# GPO.net
KiCad netlist of a schematic drawn in Altium Designer
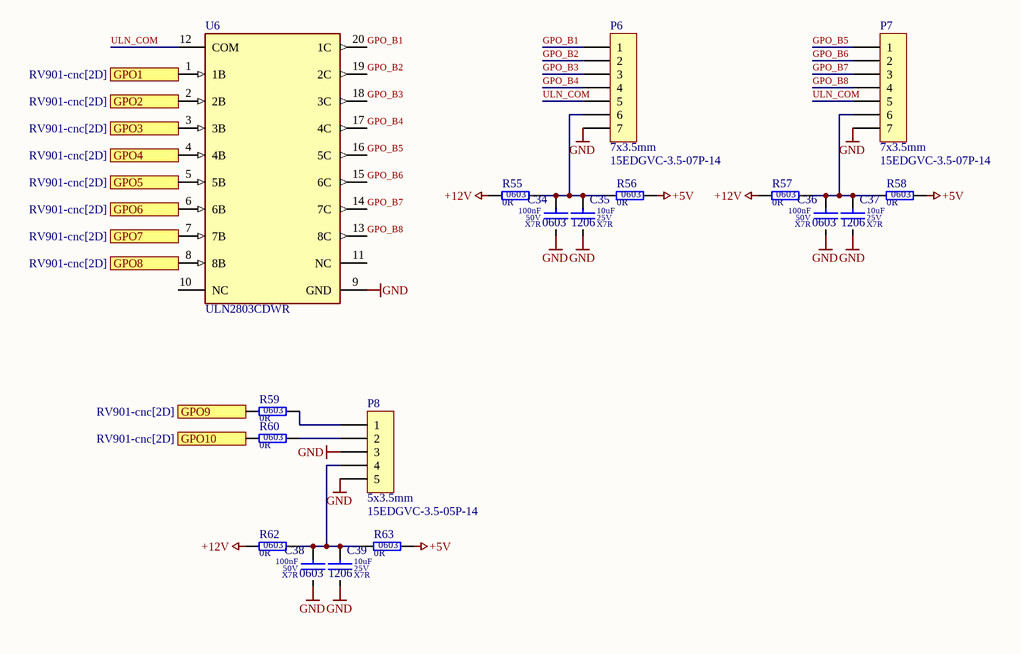
[diagram p0: GPO.SchDoc]

(export (version "E")
  (design (tool "Eeschema 10.0.6"))
  (components
    (comp (ref "C34")
      (value "100nF")
      (footprint "C_0603_1608")
      (description "Capacitor")
      (fields
        (field (name "DIELECTRIC") "X7R")
        (field (name "VOLTAGE") "50V")
        (field (name "SCH_FOOTPRINT") "0603")
        (field (name "PART NUMBER") "C_100nF_50V_X7R_0603_5")
        (field (name "MANUFACTURER") "Samsung")
      )
      (libsource (lib "Library") (part "C"))
    )
    (comp (ref "C35")
      (value "10uF")
      (footprint "C_1206_3216")
      (description "Capacitor")
      (fields
        (field (name "DIELECTRIC") "X7R")
        (field (name "VOLTAGE") "25V")
        (field (name "SCH_FOOTPRINT") "1206")
        (field (name "PART NUMBER") "C_10uF_25V_X7R_1206_10")
        (field (name "MANUFACTURER") "Samsung")
      )
      (libsource (lib "Library") (part "C"))
    )
    (comp (ref "C36")
      (value "100nF")
      (footprint "C_0603_1608")
      (description "Capacitor")
      (fields
        (field (name "DIELECTRIC") "X7R")
        (field (name "VOLTAGE") "50V")
        (field (name "SCH_FOOTPRINT") "0603")
        (field (name "PART NUMBER") "C_100nF_50V_X7R_0603_5")
        (field (name "MANUFACTURER") "Samsung")
      )
      (libsource (lib "Library") (part "C"))
    )
    (comp (ref "C37")
      (value "10uF")
      (footprint "C_1206_3216")
      (description "Capacitor")
      (fields
        (field (name "DIELECTRIC") "X7R")
        (field (name "VOLTAGE") "25V")
        (field (name "SCH_FOOTPRINT") "1206")
        (field (name "PART NUMBER") "C_10uF_25V_X7R_1206_10")
        (field (name "MANUFACTURER") "Samsung")
      )
      (libsource (lib "Library") (part "C"))
    )
    (comp (ref "C38")
      (value "100nF")
      (footprint "C_0603_1608")
      (description "Capacitor")
      (fields
        (field (name "DIELECTRIC") "X7R")
        (field (name "VOLTAGE") "50V")
        (field (name "SCH_FOOTPRINT") "0603")
        (field (name "PART NUMBER") "C_100nF_50V_X7R_0603_5")
        (field (name "MANUFACTURER") "Samsung")
      )
      (libsource (lib "Library") (part "C"))
    )
    (comp (ref "C39")
      (value "10uF")
      (footprint "C_1206_3216")
      (description "Capacitor")
      (fields
        (field (name "DIELECTRIC") "X7R")
        (field (name "VOLTAGE") "25V")
        (field (name "SCH_FOOTPRINT") "1206")
        (field (name "PART NUMBER") "C_10uF_25V_X7R_1206_10")
        (field (name "MANUFACTURER") "Samsung")
      )
      (libsource (lib "Library") (part "C"))
    )
    (comp (ref "P6")
      (value "15EDGVC-3.5-07P-14")
      (footprint "P_15EDGVC-3.5-07P")
      (description "Pin Header")
      (fields
        (field (name "SCH_FOOTPRINT") "7x3.5mm")
        (field (name "PART NUMBER") "P_15EDGVC-3.5-07P-14")
        (field (name "MANUFACTURER") "DEGSON ELECTRONICS")
      )
      (libsource (lib "Library") (part "P_HEADER_1x7"))
    )
    (comp (ref "P7")
      (value "15EDGVC-3.5-07P-14")
      (footprint "P_15EDGVC-3.5-07P")
      (description "Pin Header")
      (fields
        (field (name "SCH_FOOTPRINT") "7x3.5mm")
        (field (name "PART NUMBER") "P_15EDGVC-3.5-07P-14")
        (field (name "MANUFACTURER") "DEGSON ELECTRONICS")
      )
      (libsource (lib "Library") (part "P_HEADER_1x7"))
    )
    (comp (ref "P8")
      (value "15EDGVC-3.5-05P-14")
      (footprint "P_15EDGVC-3.5-05P")
      (description "Pin Header")
      (fields
        (field (name "SCH_FOOTPRINT") "5x3.5mm")
        (field (name "PART NUMBER") "P_15EDGVC-3.5-05P-14")
        (field (name "MANUFACTURER") "DEGSON ELECTRONICS")
      )
      (libsource (lib "Library") (part "P_HEADER_1x5"))
    )
    (comp (ref "R55")
      (value "0R")
      (footprint "R_0603_1608")
      (fields
        (field (name "SCH_FOOTPRINT") "0603")
        (field (name "PART NUMBER") "R_0R_0603_1")
        (field (name "VOLTAGE") "75V")
        (field (name "POWER") "100mW")
      )
      (libsource (lib "Library") (part "R"))
    )
    (comp (ref "R56")
      (value "0R")
      (footprint "R_0603_1608")
      (fields
        (field (name "SCH_FOOTPRINT") "0603")
        (field (name "PART NUMBER") "R_0R_0603_1")
        (field (name "VOLTAGE") "75V")
        (field (name "POWER") "100mW")
      )
      (libsource (lib "Library") (part "R"))
    )
    (comp (ref "R57")
      (value "0R")
      (footprint "R_0603_1608")
      (fields
        (field (name "SCH_FOOTPRINT") "0603")
        (field (name "PART NUMBER") "R_0R_0603_1")
        (field (name "VOLTAGE") "75V")
        (field (name "POWER") "100mW")
      )
      (libsource (lib "Library") (part "R"))
    )
    (comp (ref "R58")
      (value "0R")
      (footprint "R_0603_1608")
      (fields
        (field (name "SCH_FOOTPRINT") "0603")
        (field (name "PART NUMBER") "R_0R_0603_1")
        (field (name "VOLTAGE") "75V")
        (field (name "POWER") "100mW")
      )
      (libsource (lib "Library") (part "R"))
    )
    (comp (ref "R59")
      (value "0R")
      (footprint "R_0603_1608")
      (fields
        (field (name "SCH_FOOTPRINT") "0603")
        (field (name "PART NUMBER") "R_0R_0603_1")
        (field (name "VOLTAGE") "75V")
        (field (name "POWER") "100mW")
      )
      (libsource (lib "Library") (part "R"))
    )
    (comp (ref "R60")
      (value "0R")
      (footprint "R_0603_1608")
      (fields
        (field (name "SCH_FOOTPRINT") "0603")
        (field (name "PART NUMBER") "R_0R_0603_1")
        (field (name "VOLTAGE") "75V")
        (field (name "POWER") "100mW")
      )
      (libsource (lib "Library") (part "R"))
    )
    (comp (ref "R62")
      (value "0R")
      (footprint "R_0603_1608")
      (fields
        (field (name "SCH_FOOTPRINT") "0603")
        (field (name "PART NUMBER") "R_0R_0603_1")
        (field (name "VOLTAGE") "75V")
        (field (name "POWER") "100mW")
      )
      (libsource (lib "Library") (part "R"))
    )
    (comp (ref "R63")
      (value "0R")
      (footprint "R_0603_1608")
      (fields
        (field (name "SCH_FOOTPRINT") "0603")
        (field (name "PART NUMBER") "R_0R_0603_1")
        (field (name "VOLTAGE") "75V")
        (field (name "POWER") "100mW")
      )
      (libsource (lib "Library") (part "R"))
    )
    (comp (ref "U6")
      (value "ULN2803CDWR")
      (footprint "FP-DW0020A-MFG")
      (description "50-V, EIGHT-CHANNEL DARLINGTON A")
      (libsource (lib "Altium Content Vault") (part "1dd75b61a5dcf26d7dcab27ae8a1fe0"))
    )
  )
  (nets
    (net (code "1") (name "+5V") (class "Default")
      (node (ref "R56") (pin "2") (pinfunction "2_2") (pintype "passive"))
      (node (ref "R58") (pin "2") (pinfunction "2_2") (pintype "passive"))
      (node (ref "R63") (pin "2") (pinfunction "2_2") (pintype "passive"))
    )
    (net (code "2") (name "+12V") (class "Default")
      (node (ref "R55") (pin "1") (pinfunction "1_1") (pintype "passive"))
      (node (ref "R57") (pin "1") (pinfunction "1_1") (pintype "passive"))
      (node (ref "R62") (pin "1") (pinfunction "1_1") (pintype "passive"))
    )
    (net (code "3") (name "/GPO1") (class "Default")
      (node (ref "U6") (pin "1") (pinfunction "1B_1") (pintype "input"))
    )
    (net (code "4") (name "/GPO2") (class "Default")
      (node (ref "U6") (pin "2") (pinfunction "2B_2") (pintype "input"))
    )
    (net (code "5") (name "/GPO3") (class "Default")
      (node (ref "U6") (pin "3") (pinfunction "3B_3") (pintype "input"))
    )
    (net (code "6") (name "/GPO4") (class "Default")
      (node (ref "U6") (pin "4") (pinfunction "4B_4") (pintype "input"))
    )
    (net (code "7") (name "/GPO5") (class "Default")
      (node (ref "U6") (pin "5") (pinfunction "5B_5") (pintype "input"))
    )
    (net (code "8") (name "/GPO6") (class "Default")
      (node (ref "U6") (pin "6") (pinfunction "6B_6") (pintype "input"))
    )
    (net (code "9") (name "/GPO7") (class "Default")
      (node (ref "U6") (pin "7") (pinfunction "7B_7") (pintype "input"))
    )
    (net (code "10") (name "/GPO8") (class "Default")
      (node (ref "U6") (pin "8") (pinfunction "8B_8") (pintype "input"))
    )
    (net (code "11") (name "/GPO9") (class "Default")
      (node (ref "R59") (pin "1") (pinfunction "1_1") (pintype "passive"))
    )
    (net (code "12") (name "/GPO10") (class "Default")
      (node (ref "R60") (pin "1") (pinfunction "1_1") (pintype "passive"))
    )
    (net (code "13") (name "/GPO_B1") (class "Default")
      (node (ref "P6") (pin "1") (pinfunction "1_1") (pintype "passive"))
      (node (ref "U6") (pin "20") (pinfunction "1C_20") (pintype "output"))
    )
    (net (code "14") (name "/GPO_B2") (class "Default")
      (node (ref "P6") (pin "2") (pinfunction "2_2") (pintype "passive"))
      (node (ref "U6") (pin "19") (pinfunction "2C_19") (pintype "output"))
    )
    (net (code "15") (name "/GPO_B3") (class "Default")
      (node (ref "P6") (pin "3") (pinfunction "3_3") (pintype "passive"))
      (node (ref "U6") (pin "18") (pinfunction "3C_18") (pintype "output"))
    )
    (net (code "16") (name "/GPO_B4") (class "Default")
      (node (ref "P6") (pin "4") (pinfunction "4_4") (pintype "passive"))
      (node (ref "U6") (pin "17") (pinfunction "4C_17") (pintype "output"))
    )
    (net (code "17") (name "/GPO_B5") (class "Default")
      (node (ref "P7") (pin "1") (pinfunction "1_1") (pintype "passive"))
      (node (ref "U6") (pin "16") (pinfunction "5C_16") (pintype "output"))
    )
    (net (code "18") (name "/GPO_B6") (class "Default")
      (node (ref "P7") (pin "2") (pinfunction "2_2") (pintype "passive"))
      (node (ref "U6") (pin "15") (pinfunction "6C_15") (pintype "output"))
    )
    (net (code "19") (name "/GPO_B7") (class "Default")
      (node (ref "P7") (pin "3") (pinfunction "3_3") (pintype "passive"))
      (node (ref "U6") (pin "14") (pinfunction "7C_14") (pintype "output"))
    )
    (net (code "20") (name "/GPO_B8") (class "Default")
      (node (ref "P7") (pin "4") (pinfunction "4_4") (pintype "passive"))
      (node (ref "U6") (pin "13") (pinfunction "8C_13") (pintype "output"))
    )
    (net (code "21") (name "/ULN_COM") (class "Default")
      (node (ref "P6") (pin "5") (pinfunction "5_5") (pintype "passive"))
      (node (ref "P7") (pin "5") (pinfunction "5_5") (pintype "passive"))
      (node (ref "U6") (pin "12") (pinfunction "COM_12") (pintype "passive"))
    )
    (net (code "22") (name "GND") (class "Default")
      (node (ref "C34") (pin "2") (pinfunction "2_2") (pintype "passive"))
      (node (ref "C35") (pin "2") (pinfunction "2_2") (pintype "passive"))
      (node (ref "C36") (pin "2") (pinfunction "2_2") (pintype "passive"))
      (node (ref "C37") (pin "2") (pinfunction "2_2") (pintype "passive"))
      (node (ref "C38") (pin "2") (pinfunction "2_2") (pintype "passive"))
      (node (ref "C39") (pin "2") (pinfunction "2_2") (pintype "passive"))
      (node (ref "P6") (pin "7") (pinfunction "7_7") (pintype "passive"))
      (node (ref "P7") (pin "7") (pinfunction "7_7") (pintype "passive"))
      (node (ref "P8") (pin "3") (pinfunction "3_3") (pintype "passive"))
      (node (ref "P8") (pin "5") (pinfunction "5_5") (pintype "passive"))
      (node (ref "U6") (pin "9") (pinfunction "GND_9") (pintype "power_in"))
    )
    (net (code "23") (name "Net-(C34-Pad1)") (class "Default")
      (node (ref "C34") (pin "1") (pinfunction "1_1") (pintype "passive"))
      (node (ref "C35") (pin "1") (pinfunction "1_1") (pintype "passive"))
      (node (ref "P6") (pin "6") (pinfunction "6_6") (pintype "passive"))
      (node (ref "R55") (pin "2") (pinfunction "2_2") (pintype "passive"))
      (node (ref "R56") (pin "1") (pinfunction "1_1") (pintype "passive"))
    )
    (net (code "24") (name "Net-(C36-Pad1)") (class "Default")
      (node (ref "C36") (pin "1") (pinfunction "1_1") (pintype "passive"))
      (node (ref "C37") (pin "1") (pinfunction "1_1") (pintype "passive"))
      (node (ref "P7") (pin "6") (pinfunction "6_6") (pintype "passive"))
      (node (ref "R57") (pin "2") (pinfunction "2_2") (pintype "passive"))
      (node (ref "R58") (pin "1") (pinfunction "1_1") (pintype "passive"))
    )
    (net (code "25") (name "Net-(C38-Pad1)") (class "Default")
      (node (ref "C38") (pin "1") (pinfunction "1_1") (pintype "passive"))
      (node (ref "C39") (pin "1") (pinfunction "1_1") (pintype "passive"))
      (node (ref "P8") (pin "4") (pinfunction "4_4") (pintype "passive"))
      (node (ref "R62") (pin "2") (pinfunction "2_2") (pintype "passive"))
      (node (ref "R63") (pin "1") (pinfunction "1_1") (pintype "passive"))
    )
    (net (code "26") (name "Net-(P8-Pad1)") (class "Default")
      (node (ref "P8") (pin "1") (pinfunction "1_1") (pintype "passive"))
      (node (ref "R59") (pin "2") (pinfunction "2_2") (pintype "passive"))
    )
    (net (code "27") (name "Net-(P8-Pad2)") (class "Default")
      (node (ref "P8") (pin "2") (pinfunction "2_2") (pintype "passive"))
      (node (ref "R60") (pin "2") (pinfunction "2_2") (pintype "passive"))
    )
    (net (code "28") (name "unconnected-(U6-NC-Pad10)") (class "Default")
      (node (ref "U6") (pin "10") (pinfunction "NC_10") (pintype "passive"))
    )
    (net (code "29") (name "unconnected-(U6-NC-Pad11)") (class "Default")
      (node (ref "U6") (pin "11") (pinfunction "NC_11") (pintype "passive"))
    )
  )
)
